# CS4270-breakout.net
KiCad netlist of a schematic drawn in EAGLE
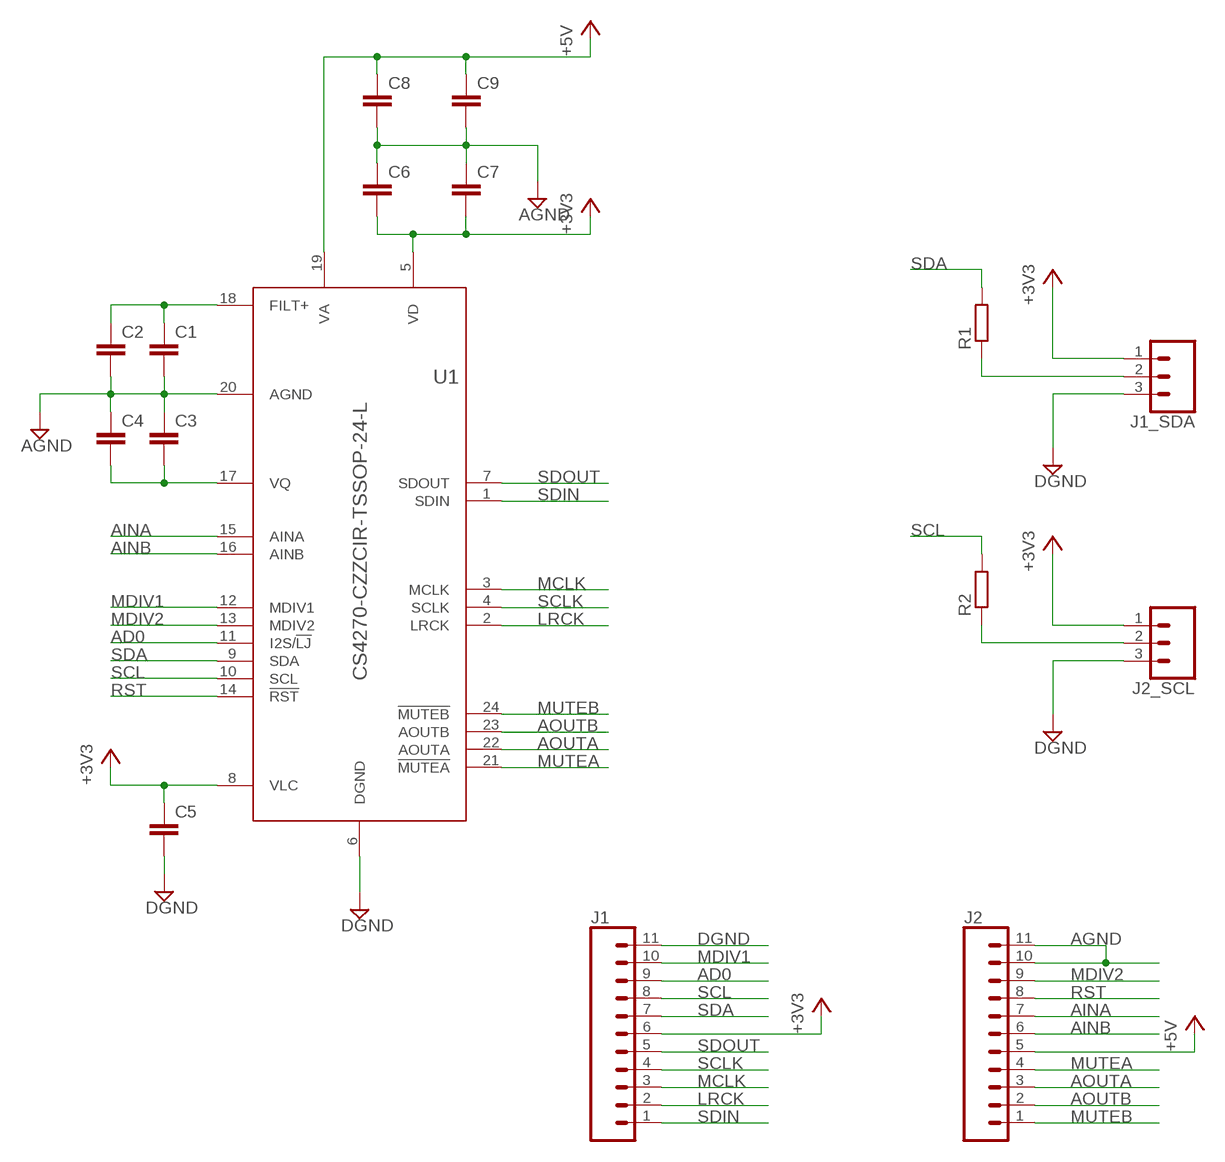
[diagram p0: schematic, sheet 1]

(export (version "E")
  (design (tool "Eeschema 10.0.6"))
  (components
    (comp (ref "C1")
      (value "CAPACITOR-EUC0603")
      (footprint "eagle-import:C0603")
      (libsource (lib "eagle-import") (part "CAPACITOR-EUC0603"))
    )
    (comp (ref "C2")
      (value "CAPACITOR-EUC0805")
      (footprint "eagle-import:C0805")
      (libsource (lib "eagle-import") (part "CAPACITOR-EUC0805"))
    )
    (comp (ref "C3")
      (value "CAPACITOR-EUC0603")
      (footprint "eagle-import:C0603")
      (libsource (lib "eagle-import") (part "CAPACITOR-EUC0603"))
    )
    (comp (ref "C4")
      (value "CAPACITOR-EUC0805")
      (footprint "eagle-import:C0805")
      (libsource (lib "eagle-import") (part "CAPACITOR-EUC0805"))
    )
    (comp (ref "C5")
      (value "CAPACITOR-EUC0603")
      (footprint "eagle-import:C0603")
      (libsource (lib "eagle-import") (part "CAPACITOR-EUC0603"))
    )
    (comp (ref "C6")
      (value "CAPACITOR-EUC0603")
      (footprint "eagle-import:C0603")
      (libsource (lib "eagle-import") (part "CAPACITOR-EUC0603"))
    )
    (comp (ref "C7")
      (value "CAPACITOR-EUC0603")
      (footprint "eagle-import:C0603")
      (libsource (lib "eagle-import") (part "CAPACITOR-EUC0603"))
    )
    (comp (ref "C8")
      (value "CAPACITOR-EUC0603")
      (footprint "eagle-import:C0603")
      (libsource (lib "eagle-import") (part "CAPACITOR-EUC0603"))
    )
    (comp (ref "C9")
      (value "CAPACITOR-EUC0603")
      (footprint "eagle-import:C0603")
      (libsource (lib "eagle-import") (part "CAPACITOR-EUC0603"))
    )
    (comp (ref "J1")
      (value "CONN_11LOCK")
      (footprint "eagle-import:1X11_LOCK")
      (libsource (lib "eagle-import") (part "CONN_11LOCK"))
    )
    (comp (ref "J1_SDA")
      (value "CONN_03LOCK")
      (footprint "eagle-import:1X03_LOCK")
      (libsource (lib "eagle-import") (part "CONN_03LOCK"))
    )
    (comp (ref "J2")
      (value "CONN_11LOCK")
      (footprint "eagle-import:1X11_LOCK")
      (libsource (lib "eagle-import") (part "CONN_11LOCK"))
    )
    (comp (ref "J2_SCL")
      (value "CONN_03LOCK")
      (footprint "eagle-import:1X03_LOCK")
      (libsource (lib "eagle-import") (part "CONN_03LOCK"))
    )
    (comp (ref "R1")
      (value "RESISTOR-EU_R0603")
      (footprint "eagle-import:R0603")
      (libsource (lib "eagle-import") (part "RESISTOR-EU_R0603"))
    )
    (comp (ref "R2")
      (value "RESISTOR-EU_R0603")
      (footprint "eagle-import:R0603")
      (libsource (lib "eagle-import") (part "RESISTOR-EU_R0603"))
    )
    (comp (ref "U1")
      (value "CS4270-CZZCIR-TSSOP-24-L")
      (footprint "eagle-import:CIR-TSSOP-24-L")
      (fields (field (name "MANUFACTURER_PART_NUMBER") "CS4270CZZ"))
      (libsource (lib "eagle-import") (part "CS4270-CZZCIR-TSSOP-24-L"))
    )
  )
  (nets
    (net (code "1") (name "+3V3") (class "Default")
      (node (ref "C5") (pin "1") (pinfunction "1_1") (pintype "passive"))
      (node (ref "C6") (pin "2") (pinfunction "2_2") (pintype "passive"))
      (node (ref "C7") (pin "2") (pinfunction "2_2") (pintype "passive"))
      (node (ref "J1") (pin "6") (pinfunction "6_6") (pintype "passive"))
      (node (ref "J1_SDA") (pin "1") (pinfunction "1_1") (pintype "passive"))
      (node (ref "J2_SCL") (pin "1") (pinfunction "1_1") (pintype "passive"))
      (node (ref "U1") (pin "5") (pinfunction "VD_5") (pintype "power_in"))
      (node (ref "U1") (pin "8") (pinfunction "VLC_8") (pintype "power_in"))
    )
    (net (code "2") (name "+5V") (class "Default")
      (node (ref "C8") (pin "1") (pinfunction "1_1") (pintype "passive"))
      (node (ref "C9") (pin "1") (pinfunction "1_1") (pintype "passive"))
      (node (ref "J2") (pin "5") (pinfunction "5_5") (pintype "passive"))
      (node (ref "U1") (pin "19") (pinfunction "VA_19") (pintype "power_in"))
    )
    (net (code "3") (name "/AD0") (class "Default")
      (node (ref "J1") (pin "9") (pinfunction "9_9") (pintype "passive"))
      (node (ref "U1") (pin "11") (pinfunction "I2S/~{LJ}_11") (pintype "input"))
    )
    (net (code "4") (name "/AINA") (class "Default")
      (node (ref "J2") (pin "7") (pinfunction "7_7") (pintype "passive"))
      (node (ref "U1") (pin "15") (pinfunction "AINA_15") (pintype "input"))
    )
    (net (code "5") (name "/AINB") (class "Default")
      (node (ref "J2") (pin "6") (pinfunction "6_6") (pintype "passive"))
      (node (ref "U1") (pin "16") (pinfunction "AINB_16") (pintype "input"))
    )
    (net (code "6") (name "/AOUTA") (class "Default")
      (node (ref "J2") (pin "3") (pinfunction "3_3") (pintype "passive"))
      (node (ref "U1") (pin "22") (pinfunction "AOUTA_22") (pintype "output"))
    )
    (net (code "7") (name "/AOUTB") (class "Default")
      (node (ref "J2") (pin "2") (pinfunction "2_2") (pintype "passive"))
      (node (ref "U1") (pin "23") (pinfunction "AOUTB_23") (pintype "output"))
    )
    (net (code "8") (name "/LRCK") (class "Default")
      (node (ref "J1") (pin "2") (pinfunction "2_2") (pintype "passive"))
      (node (ref "U1") (pin "2") (pinfunction "LRCK_2") (pintype "bidirectional"))
    )
    (net (code "9") (name "/MCLK") (class "Default")
      (node (ref "J1") (pin "3") (pinfunction "3_3") (pintype "passive"))
      (node (ref "U1") (pin "3") (pinfunction "MCLK_3") (pintype "input"))
    )
    (net (code "10") (name "/MDIV1") (class "Default")
      (node (ref "J1") (pin "10") (pinfunction "10_10") (pintype "passive"))
      (node (ref "U1") (pin "12") (pinfunction "MDIV1_12") (pintype "input"))
    )
    (net (code "11") (name "/MDIV2") (class "Default")
      (node (ref "J2") (pin "9") (pinfunction "9_9") (pintype "passive"))
      (node (ref "U1") (pin "13") (pinfunction "MDIV2_13") (pintype "input"))
    )
    (net (code "12") (name "/MUTEA") (class "Default")
      (node (ref "J2") (pin "4") (pinfunction "4_4") (pintype "passive"))
      (node (ref "U1") (pin "21") (pinfunction "~{MUTEA}_21") (pintype "output"))
    )
    (net (code "13") (name "/MUTEB") (class "Default")
      (node (ref "J2") (pin "1") (pinfunction "1_1") (pintype "passive"))
      (node (ref "U1") (pin "24") (pinfunction "~{MUTEB}_24") (pintype "output"))
    )
    (net (code "14") (name "/RST") (class "Default")
      (node (ref "J2") (pin "8") (pinfunction "8_8") (pintype "passive"))
      (node (ref "U1") (pin "14") (pinfunction "~{RST}_14") (pintype "input"))
    )
    (net (code "15") (name "/SCL") (class "Default")
      (node (ref "J1") (pin "8") (pinfunction "8_8") (pintype "passive"))
      (node (ref "R2") (pin "2") (pinfunction "2_2") (pintype "passive"))
      (node (ref "U1") (pin "10") (pinfunction "SCL_10") (pintype "input"))
    )
    (net (code "16") (name "/SCLK") (class "Default")
      (node (ref "J1") (pin "4") (pinfunction "4_4") (pintype "passive"))
      (node (ref "U1") (pin "4") (pinfunction "SCLK_4") (pintype "bidirectional"))
    )
    (net (code "17") (name "/SDA") (class "Default")
      (node (ref "J1") (pin "7") (pinfunction "7_7") (pintype "passive"))
      (node (ref "R1") (pin "2") (pinfunction "2_2") (pintype "passive"))
      (node (ref "U1") (pin "9") (pinfunction "SDA_9") (pintype "input"))
    )
    (net (code "18") (name "/SDIN") (class "Default")
      (node (ref "J1") (pin "1") (pinfunction "1_1") (pintype "passive"))
      (node (ref "U1") (pin "1") (pinfunction "SDIN_1") (pintype "input"))
    )
    (net (code "19") (name "/SDOUT") (class "Default")
      (node (ref "J1") (pin "5") (pinfunction "5_5") (pintype "passive"))
      (node (ref "U1") (pin "7") (pinfunction "SDOUT_7") (pintype "output"))
    )
    (net (code "20") (name "AGND") (class "Default")
      (node (ref "C1") (pin "2") (pinfunction "2_2") (pintype "passive"))
      (node (ref "C2") (pin "2") (pinfunction "2_2") (pintype "passive"))
      (node (ref "C3") (pin "1") (pinfunction "1_1") (pintype "passive"))
      (node (ref "C4") (pin "1") (pinfunction "1_1") (pintype "passive"))
      (node (ref "C6") (pin "1") (pinfunction "1_1") (pintype "passive"))
      (node (ref "C7") (pin "1") (pinfunction "1_1") (pintype "passive"))
      (node (ref "C8") (pin "2") (pinfunction "2_2") (pintype "passive"))
      (node (ref "C9") (pin "2") (pinfunction "2_2") (pintype "passive"))
      (node (ref "J2") (pin "10") (pinfunction "10_10") (pintype "passive"))
      (node (ref "J2") (pin "11") (pinfunction "11_11") (pintype "passive"))
      (node (ref "U1") (pin "20") (pinfunction "AGND_20") (pintype "power_in"))
    )
    (net (code "21") (name "DGND") (class "Default")
      (node (ref "C5") (pin "2") (pinfunction "2_2") (pintype "passive"))
      (node (ref "J1") (pin "11") (pinfunction "11_11") (pintype "passive"))
      (node (ref "J1_SDA") (pin "3") (pinfunction "3_3") (pintype "passive"))
      (node (ref "J2_SCL") (pin "3") (pinfunction "3_3") (pintype "passive"))
      (node (ref "U1") (pin "6") (pinfunction "DGND_6") (pintype "power_in"))
    )
    (net (code "22") (name "Net-(J1_SDA-Pad2)") (class "Default")
      (node (ref "J1_SDA") (pin "2") (pinfunction "2_2") (pintype "passive"))
      (node (ref "R1") (pin "1") (pinfunction "1_1") (pintype "passive"))
    )
    (net (code "23") (name "Net-(J2_SCL-Pad2)") (class "Default")
      (node (ref "J2_SCL") (pin "2") (pinfunction "2_2") (pintype "passive"))
      (node (ref "R2") (pin "1") (pinfunction "1_1") (pintype "passive"))
    )
    (net (code "24") (name "Net-(U1-FILT+)") (class "Default")
      (node (ref "C1") (pin "1") (pinfunction "1_1") (pintype "passive"))
      (node (ref "C2") (pin "1") (pinfunction "1_1") (pintype "passive"))
      (node (ref "U1") (pin "18") (pinfunction "FILT+_18") (pintype "output"))
    )
    (net (code "25") (name "Net-(U1-VQ)") (class "Default")
      (node (ref "C3") (pin "2") (pinfunction "2_2") (pintype "passive"))
      (node (ref "C4") (pin "2") (pinfunction "2_2") (pintype "passive"))
      (node (ref "U1") (pin "17") (pinfunction "VQ_17") (pintype "output"))
    )
  )
)
